# Sheet1.net
KiCad netlist of a schematic drawn in Altium Designer
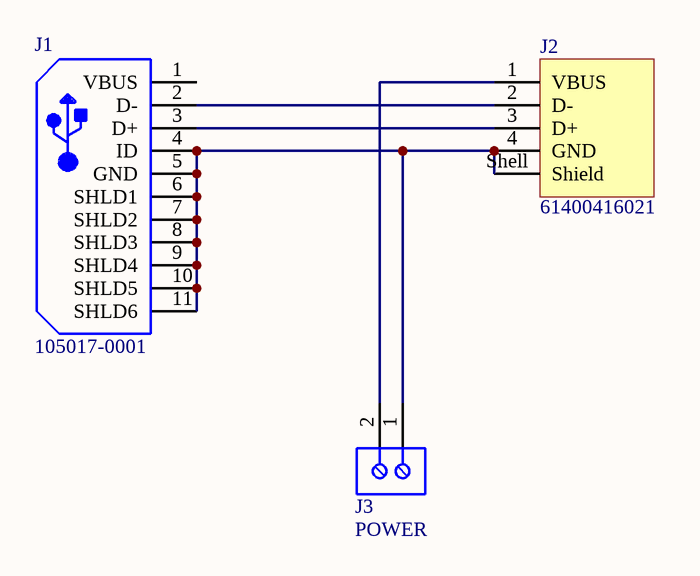
[diagram p0: Sheet1.SchDoc]

(export (version "E")
  (design (tool "Eeschema 10.0.6"))
  (components
    (comp (ref "J1")
      (value "105017-0001")
      (footprint "USB-MICRO-B_V")
      (fields (field (name "MANUFACTURER") "Molex"))
      (libsource (lib "Altium Content Vault") (part "USB-5-6SHLD"))
    )
    (comp (ref "J2")
      (value "61400416021")
      (footprint "61400416021")
      (libsource (lib "Altium Content Vault") (part "USB 2.0_Type A_Receptacle_1 Port"))
    )
    (comp (ref "J3")
      (value "POWER")
      (footprint "691102710002")
      (fields (field (name "VOLTAGE") "300V"))
      (libsource (lib "Altium Content Vault") (part "TBL - 1R - 02P - Screw"))
    )
  )
  (nets
    (net (code "1") (name "Net-(J1-D+)") (class "Default")
      (node (ref "J1") (pin "3") (pinfunction "D+_3") (pintype "passive"))
      (node (ref "J2") (pin "3") (pinfunction "D+_3") (pintype "passive"))
    )
    (net (code "2") (name "Net-(J1-D-)") (class "Default")
      (node (ref "J1") (pin "2") (pinfunction "D-_2") (pintype "passive"))
      (node (ref "J2") (pin "2") (pinfunction "D-_2") (pintype "passive"))
    )
    (net (code "3") (name "Net-(J1-GND)") (class "Default")
      (node (ref "J1") (pin "10") (pinfunction "SHLD5_10") (pintype "passive"))
      (node (ref "J1") (pin "11") (pinfunction "SHLD6_11") (pintype "passive"))
      (node (ref "J1") (pin "4") (pinfunction "ID_4") (pintype "passive"))
      (node (ref "J1") (pin "5") (pinfunction "GND_5") (pintype "passive"))
      (node (ref "J1") (pin "6") (pinfunction "SHLD1_6") (pintype "passive"))
      (node (ref "J1") (pin "7") (pinfunction "SHLD2_7") (pintype "passive"))
      (node (ref "J1") (pin "8") (pinfunction "SHLD3_8") (pintype "passive"))
      (node (ref "J1") (pin "9") (pinfunction "SHLD4_9") (pintype "passive"))
      (node (ref "J2") (pin "4") (pinfunction "GND_4") (pintype "passive"))
      (node (ref "J2") (pin "Shell") (pinfunction "Shield_Shell") (pintype "passive"))
      (node (ref "J3") (pin "1") (pinfunction "1_1") (pintype "passive"))
    )
    (net (code "4") (name "Net-(J2-VBUS)") (class "Default")
      (node (ref "J2") (pin "1") (pinfunction "VBUS_1") (pintype "passive"))
      (node (ref "J3") (pin "2") (pinfunction "2_2") (pintype "passive"))
    )
    (net (code "5") (name "unconnected-(J1-VBUS-Pad1)") (class "Default")
      (node (ref "J1") (pin "1") (pinfunction "VBUS_1") (pintype "passive"))
    )
  )
)
